# LPS_3_3v_0_6A_6V_AP2112K-3_3TRG1.net
KiCad netlist of a schematic drawn in Altium Designer
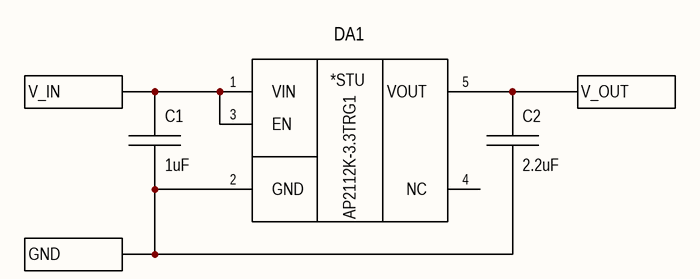
[diagram p0: LPS 3.3v 0.6A (6V) AP2112K-3.3TRG1.SchDoc]

(export (version "E")
  (design (tool "Eeschema 10.0.6"))
  (components
    (comp (ref "C1")
      (value "1uF")
      (footprint "CAPC1608L")
      (description "Capacitor Ceramic 1uF 25V 0603(1608)")
      (fields (field (name "TOLERANCE") "±10%") (field (name "VOLTAGE") "25V"))
      (libsource (lib "Capacitors") (part "Capacitor Ceramic 1uF 25V 0603(1608)"))
    )
    (comp (ref "C2")
      (value "2.2uF")
      (footprint "CAPC2012L")
      (description "Capacitor Ceramic 2.2uF 50V 0805(2012)")
      (fields (field (name "TOLERANCE") "±10%") (field (name "VOLTAGE") "50V"))
      (libsource (lib "Capacitors") (part "Capacitor Ceramic 2.2uF 50V 0805(2012)"))
    )
    (comp (ref "DA1")
      (value "AP2112K-3.3TRG1")
      (footprint "SOT-23-5")
      (description "LDO 0.6A 3.3V (6V)")
      (fields (field (name "MANUFACTURER") "Diodes Incorporated"))
      (libsource (lib "Power") (part "AP2112K-3.3TRG1"))
    )
  )
  (nets
    (net (code "1") (name "/GND") (class "Default")
      (node (ref "C1") (pin "2") (pinfunction "2_2") (pintype "passive"))
      (node (ref "C2") (pin "2") (pinfunction "2_2") (pintype "passive"))
      (node (ref "DA1") (pin "2") (pinfunction "GND_2") (pintype "passive"))
    )
    (net (code "2") (name "/V_IN") (class "Default")
      (node (ref "C1") (pin "1") (pinfunction "1_1") (pintype "passive"))
      (node (ref "DA1") (pin "1") (pinfunction "VIN_1") (pintype "passive"))
      (node (ref "DA1") (pin "3") (pinfunction "EN_3") (pintype "passive"))
    )
    (net (code "3") (name "/V_OUT") (class "Default")
      (node (ref "C2") (pin "1") (pinfunction "1_1") (pintype "passive"))
      (node (ref "DA1") (pin "5") (pinfunction "VOUT_5") (pintype "passive"))
    )
    (net (code "4") (name "unconnected-(DA1-NC-Pad4)") (class "Default")
      (node (ref "DA1") (pin "4") (pinfunction "NC_4") (pintype "passive"))
    )
  )
)
